# MP2565_dev_v1-eagle_7_6.net
KiCad netlist of a schematic drawn in EAGLE
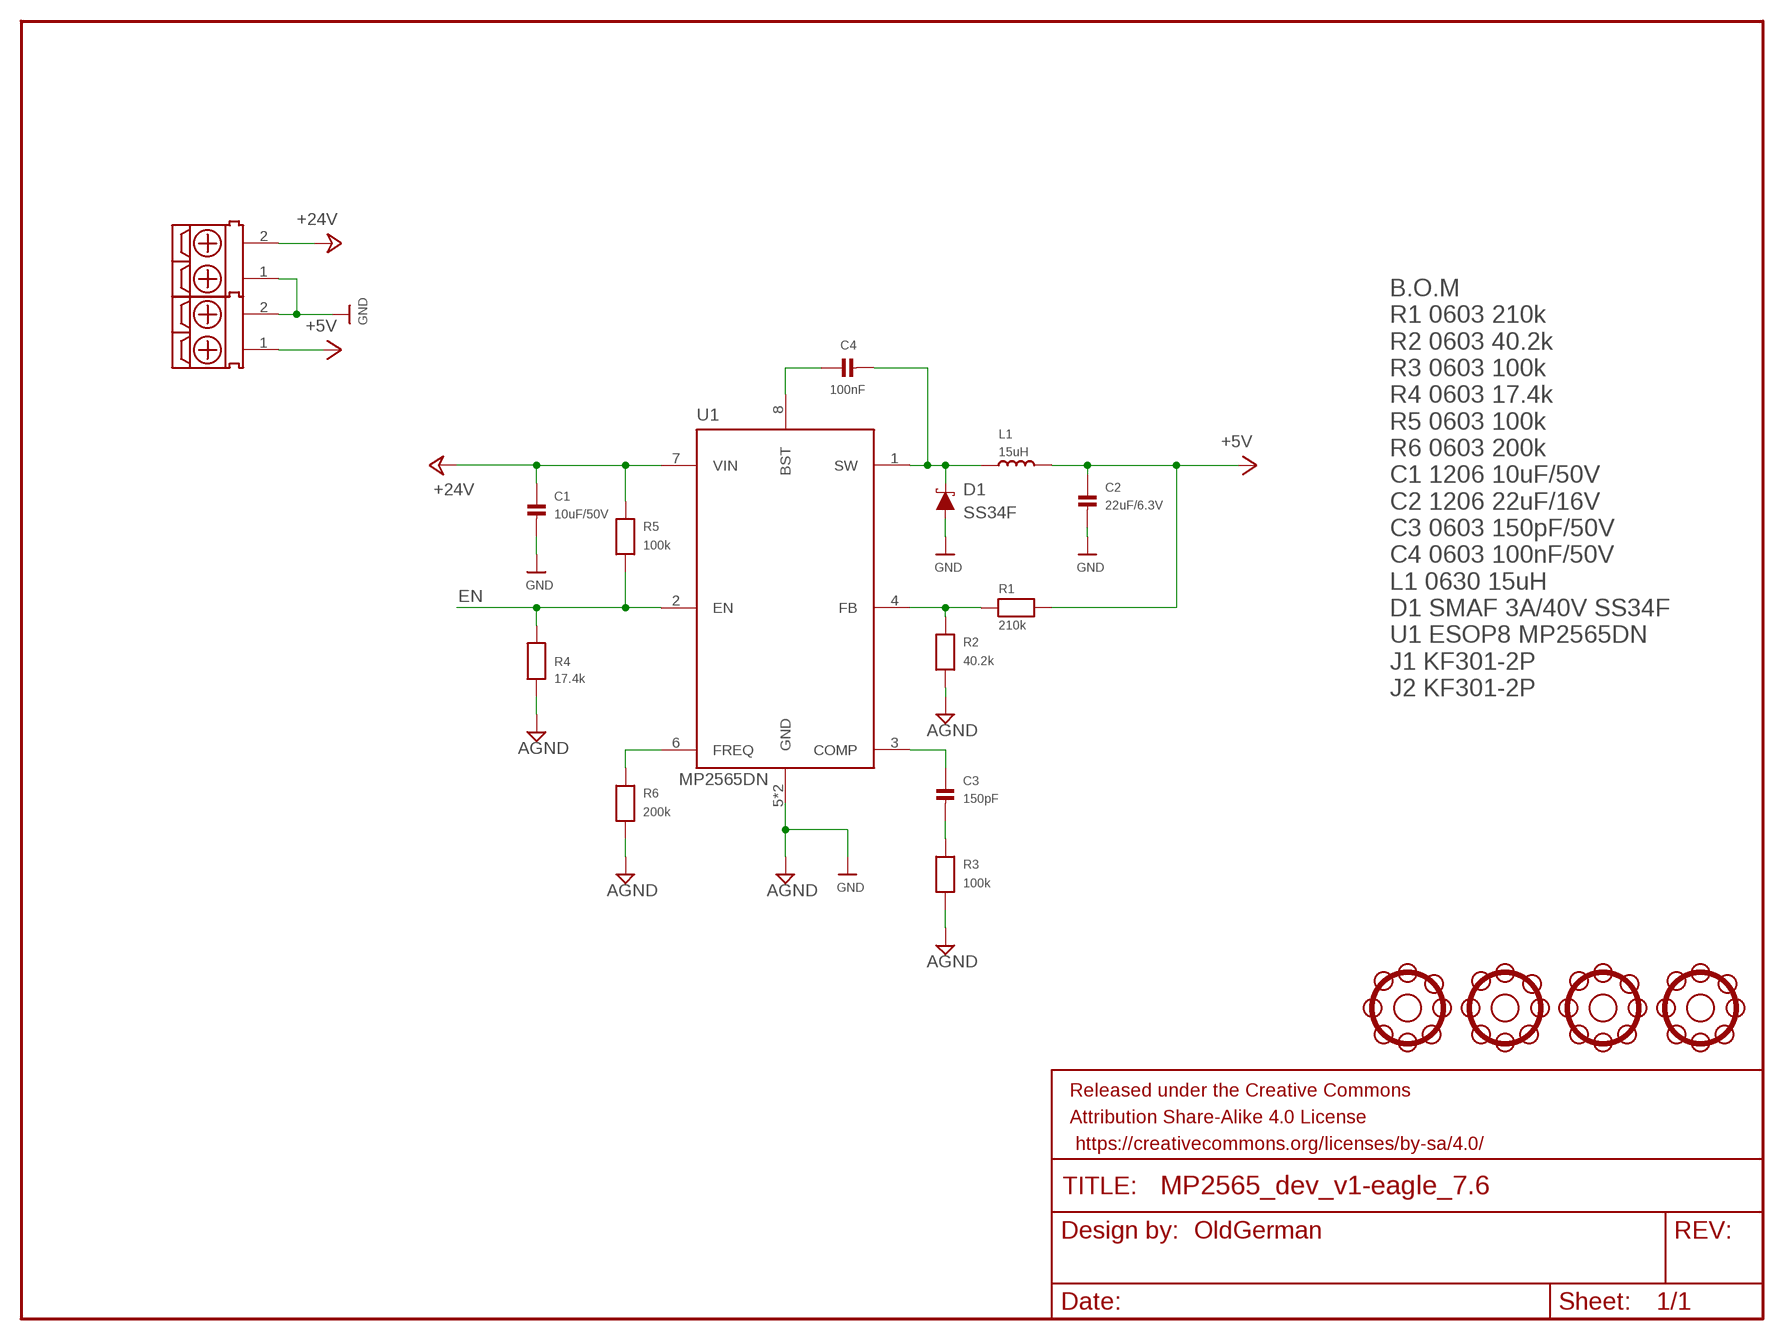
[diagram p0: schematic, sheet 1]

(export (version "E")
  (design (tool "Eeschema 10.0.6"))
  (components
    (comp (ref "C1")
      (value "10uF/50V")
      (footprint "eagle-import:1206")
      (libsource (lib "eagle-import") (part "CAP_CERAMIC1206"))
    )
    (comp (ref "C2")
      (value "22uF/6.3V")
      (footprint "eagle-import:1206")
      (libsource (lib "eagle-import") (part "CAP_CERAMIC1206"))
    )
    (comp (ref "C3")
      (value "150pF")
      (footprint "eagle-import:0603")
      (libsource (lib "eagle-import") (part "CAP_CERAMIC0603"))
    )
    (comp (ref "C4")
      (value "100nF")
      (footprint "eagle-import:0603")
      (libsource (lib "eagle-import") (part "CAP_CERAMIC0603"))
    )
    (comp (ref "D1")
      (value "SS34F")
      (footprint "eagle-import:SMAF")
      (libsource (lib "eagle-import") (part "SS34F"))
    )
    (comp (ref "FRAME1")
      (value "FRAME-LETTER")
      (footprint "eagle-import:CREATIVE_COMMONS")
      (libsource (lib "eagle-import") (part "FRAME-LETTER"))
    )
    (comp (ref "J1")
      (value "KF301_2P-5.0MM")
      (footprint "eagle-import:KF301__2P-5.0MM")
      (libsource (lib "eagle-import") (part "KF301_2P-5.0MM"))
    )
    (comp (ref "J2")
      (value "KF301_2P-5.0MM")
      (footprint "eagle-import:KF301__2P-5.0MM")
      (libsource (lib "eagle-import") (part "KF301_2P-5.0MM"))
    )
    (comp (ref "L1")
      (value "15uH")
      (footprint "eagle-import:L0630")
      (libsource (lib "eagle-import") (part "INDUCTOR'0630'"))
    )
    (comp (ref "R1")
      (value "210k")
      (footprint "eagle-import:0603")
      (libsource (lib "eagle-import") (part "RESISTOR0603"))
    )
    (comp (ref "R2")
      (value "40.2k")
      (footprint "eagle-import:0603")
      (libsource (lib "eagle-import") (part "RESISTOR0603"))
    )
    (comp (ref "R3")
      (value "100k")
      (footprint "eagle-import:0603")
      (libsource (lib "eagle-import") (part "RESISTOR0603"))
    )
    (comp (ref "R4")
      (value "17.4k")
      (footprint "eagle-import:0603")
      (libsource (lib "eagle-import") (part "RESISTOR0603"))
    )
    (comp (ref "R5")
      (value "100k")
      (footprint "eagle-import:0603")
      (libsource (lib "eagle-import") (part "RESISTOR0603"))
    )
    (comp (ref "R6")
      (value "200k")
      (footprint "eagle-import:0603")
      (libsource (lib "eagle-import") (part "RESISTOR0603"))
    )
    (comp (ref "U$13")
      (value "SUN_HOLE_M3")
      (footprint "eagle-import:SUN_HOLE_M3")
      (libsource (lib "eagle-import") (part "SUN_HOLE_M3"))
    )
    (comp (ref "U$14")
      (value "SUN_HOLE_M3")
      (footprint "eagle-import:SUN_HOLE_M3")
      (libsource (lib "eagle-import") (part "SUN_HOLE_M3"))
    )
    (comp (ref "U$15")
      (value "SUN_HOLE_M3")
      (footprint "eagle-import:SUN_HOLE_M3")
      (libsource (lib "eagle-import") (part "SUN_HOLE_M3"))
    )
    (comp (ref "U$16")
      (value "SUN_HOLE_M3")
      (footprint "eagle-import:SUN_HOLE_M3")
      (libsource (lib "eagle-import") (part "SUN_HOLE_M3"))
    )
    (comp (ref "U1")
      (value "MP2565DN")
      (footprint "eagle-import:ESOP8L-1.27-5X3.9MM")
      (libsource (lib "eagle-import") (part "MP2565DN"))
    )
  )
  (nets
    (net (code "1") (name "+5V") (class "Default")
      (node (ref "C2") (pin "1") (pinfunction "P$1_1") (pintype "passive"))
      (node (ref "J2") (pin "1") (pinfunction "P$1_1") (pintype "bidirectional"))
      (node (ref "L1") (pin "2") (pinfunction "2_2") (pintype "passive"))
      (node (ref "R1") (pin "2") (pinfunction "2_2") (pintype "passive"))
    )
    (net (code "2") (name "+24V") (class "Default")
      (node (ref "C1") (pin "1") (pinfunction "P$1_1") (pintype "passive"))
      (node (ref "J1") (pin "2") (pinfunction "P$2_2") (pintype "bidirectional"))
      (node (ref "R5") (pin "2") (pinfunction "2_2") (pintype "passive"))
      (node (ref "U1") (pin "7") (pinfunction "VIN_7") (pintype "bidirectional"))
    )
    (net (code "3") (name "/EN") (class "Default")
      (node (ref "R4") (pin "1") (pinfunction "1_1") (pintype "passive"))
      (node (ref "R5") (pin "1") (pinfunction "1_1") (pintype "passive"))
      (node (ref "U1") (pin "2") (pinfunction "EN_2") (pintype "bidirectional"))
    )
    (net (code "4") (name "AGND") (class "Default")
      (node (ref "C1") (pin "2") (pinfunction "P$2_2") (pintype "passive"))
      (node (ref "C2") (pin "2") (pinfunction "P$2_2") (pintype "passive"))
      (node (ref "D1") (pin "A") (pinfunction "A_A") (pintype "passive"))
      (node (ref "J1") (pin "1") (pinfunction "P$1_1") (pintype "bidirectional"))
      (node (ref "J2") (pin "2") (pinfunction "P$2_2") (pintype "bidirectional"))
      (node (ref "R2") (pin "1") (pinfunction "1_1") (pintype "passive"))
      (node (ref "R3") (pin "1") (pinfunction "1_1") (pintype "passive"))
      (node (ref "R4") (pin "2") (pinfunction "2_2") (pintype "passive"))
      (node (ref "R6") (pin "1") (pinfunction "1_1") (pintype "passive"))
      (node (ref "U1") (pin "5") (pinfunction "GND_5") (pintype "bidirectional"))
      (node (ref "U1") (pin "PAD") (pinfunction "GND_PAD") (pintype "bidirectional"))
    )
    (net (code "5") (name "Net-(C3-P$1)") (class "Default")
      (node (ref "C3") (pin "1") (pinfunction "P$1_1") (pintype "passive"))
      (node (ref "U1") (pin "3") (pinfunction "COMP_3") (pintype "bidirectional"))
    )
    (net (code "6") (name "Net-(C3-P$2)") (class "Default")
      (node (ref "C3") (pin "2") (pinfunction "P$2_2") (pintype "passive"))
      (node (ref "R3") (pin "2") (pinfunction "2_2") (pintype "passive"))
    )
    (net (code "7") (name "Net-(C4-P$1)") (class "Default")
      (node (ref "C4") (pin "1") (pinfunction "P$1_1") (pintype "passive"))
      (node (ref "U1") (pin "8") (pinfunction "BST_8") (pintype "bidirectional"))
    )
    (net (code "8") (name "Net-(C4-P$2)") (class "Default")
      (node (ref "C4") (pin "2") (pinfunction "P$2_2") (pintype "passive"))
      (node (ref "D1") (pin "C") (pinfunction "C_C") (pintype "passive"))
      (node (ref "L1") (pin "1") (pinfunction "1_1") (pintype "passive"))
      (node (ref "U1") (pin "1") (pinfunction "SW_1") (pintype "bidirectional"))
    )
    (net (code "9") (name "Net-(U1-FB)") (class "Default")
      (node (ref "R1") (pin "1") (pinfunction "1_1") (pintype "passive"))
      (node (ref "R2") (pin "2") (pinfunction "2_2") (pintype "passive"))
      (node (ref "U1") (pin "4") (pinfunction "FB_4") (pintype "bidirectional"))
    )
    (net (code "10") (name "Net-(U1-FREQ)") (class "Default")
      (node (ref "R6") (pin "2") (pinfunction "2_2") (pintype "passive"))
      (node (ref "U1") (pin "6") (pinfunction "FREQ_6") (pintype "bidirectional"))
    )
  )
)
